# SME_tps63021.net
KiCad netlist of a schematic drawn in Altium Designer
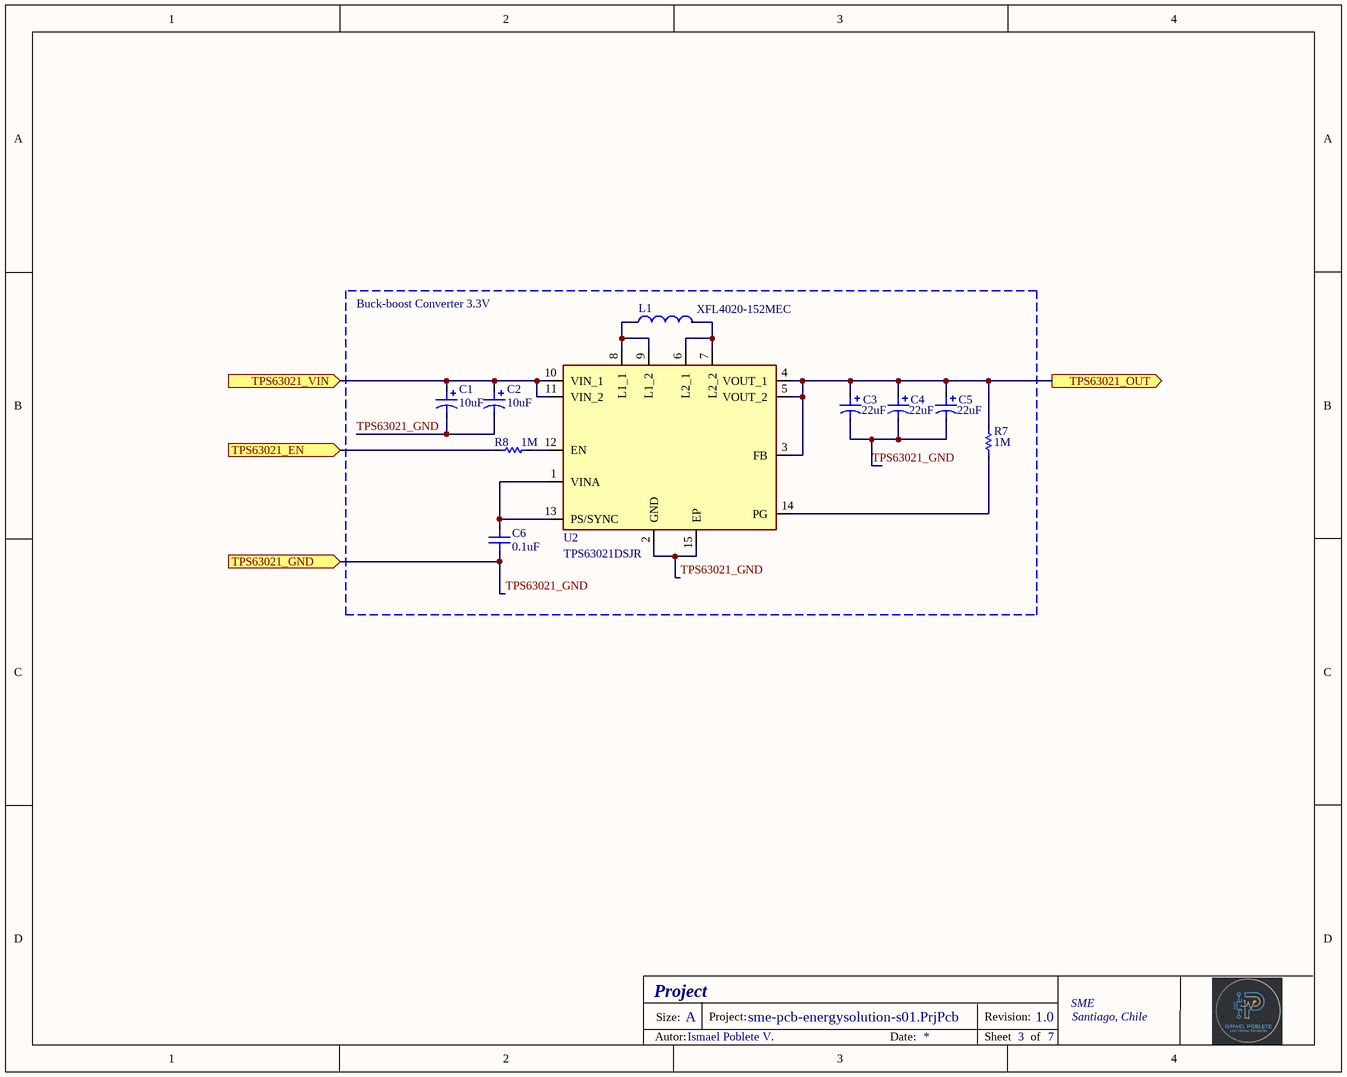
[diagram p0: SME_tps63021.SchDoc]

(export (version "E")
  (design (tool "Eeschema 10.0.6"))
  (components
    (comp (ref "C1")
      (value "T491A106M016AT")
      (footprint "CASE_A")
      (fields
        (field (name "MANUFACTURER") "Yageo Group")
        (field (name "TOLERANCE") "10%")
        (field (name "VOLTAGE") "16V")
        (field (name "CAPACITANCE") "10uF")
      )
      (libsource (lib "SME") (part "T491A106M016AT"))
    )
    (comp (ref "C2")
      (value "T491A106M016AT")
      (footprint "CASE_A")
      (fields
        (field (name "MANUFACTURER") "Yageo Group")
        (field (name "TOLERANCE") "10%")
        (field (name "VOLTAGE") "16V")
        (field (name "CAPACITANCE") "10uF")
      )
      (libsource (lib "SME") (part "T491A106M016AT"))
    )
    (comp (ref "C3")
      (value "T491B226K006AT")
      (footprint "T491B / CASE_B")
      (description "Tantalum Capacitors - Solid SMD 6.3V 22uF 1311 10% ESR=3.5ohms")
      (fields (field (name "CAPACITANCE") "22uF") (field (name "MANUFACTURER") "Yageo Group"))
      (libsource (lib "SME") (part "T491B226K006AT"))
    )
    (comp (ref "C4")
      (value "T491B226K006AT")
      (footprint "T491B / CASE_B")
      (description "Tantalum Capacitors - Solid SMD 6.3V 22uF 1311 10% ESR=3.5ohms")
      (fields (field (name "CAPACITANCE") "22uF") (field (name "MANUFACTURER") "Yageo Group"))
      (libsource (lib "SME") (part "T491B226K006AT"))
    )
    (comp (ref "C5")
      (value "T491B226K006AT")
      (footprint "T491B / CASE_B")
      (description "Tantalum Capacitors - Solid SMD 6.3V 22uF 1311 10% ESR=3.5ohms")
      (fields (field (name "CAPACITANCE") "22uF") (field (name "MANUFACTURER") "Yageo Group"))
      (libsource (lib "SME") (part "T491B226K006AT"))
    )
    (comp (ref "C6")
      (value "CC0603KRX7R9BB104")
      (footprint "C0603")
      (description "Multilayer Ceramic Capacitors MLCC - SMD/SMT 50 V 0.1uF X7R 0603 10%")
      (fields (field (name "CAPACITANCE") "0.1uF") (field (name "MANUFACTURER") "Yageo Group"))
      (libsource (lib "SME") (part "CC0603KRX7R9BB104"))
    )
    (comp (ref "L1")
      (value "XFL4020-152MEC")
      (footprint "XFL4020152MEC")
      (description "COILCRAFT - XFL4020-152MEC - Power Inductor (SMD), 1.5 H, 9.1 A, Shielded, 4.1 A, XFL4020")
      (fields
        (field (name "MOUSER PART NUMBER") "994-XFL4020-152MEC")
        (field (name "MANUFACTURER") "Coilcraft")
      )
      (libsource (lib "SME") (part "XFL4020-152MEC"))
    )
    (comp (ref "R7")
      (value "RT0603FRE071ML")
      (footprint "RES_0603")
      (description "Thin Film Resistors - SMD 1M OHM 1% 50PPM 1/10 W")
      (fields (field (name "RESISTANCE") "1M") (field (name "MANUFACTURER") "Yageo Group"))
      (libsource (lib "SME") (part "RT0603FRE071ML"))
    )
    (comp (ref "R8")
      (value "RT0603FRE071ML")
      (footprint "RES_0603")
      (description "Thin Film Resistors - SMD 1M OHM 1% 50PPM 1/10 W")
      (fields (field (name "RESISTANCE") "1M") (field (name "MANUFACTURER") "Yageo Group"))
      (libsource (lib "SME") (part "RT0603FRE071ML"))
    )
    (comp (ref "U2")
      (value "TPS63021DSJR")
      (footprint "VSON-14")
      (description "High Efficiency Single Inductor Buck-Boost Converter with 4A Switch")
      (fields
        (field (name "MOUSER PART NUMBER") "595-TPS63021DSJR")
        (field (name "MANUFACTURER") "Texas Instruments")
      )
      (libsource (lib "SME") (part "TPS63021DSJR"))
    )
  )
  (nets
    (net (code "1") (name "/TPS63021_EN") (class "Default")
      (node (ref "R8") (pin "1") (pinfunction "1_1") (pintype "passive"))
    )
    (net (code "2") (name "/TPS63021_GND") (class "Default")
      (node (ref "C1") (pin "2") (pinfunction "2_2") (pintype "passive"))
      (node (ref "C2") (pin "2") (pinfunction "2_2") (pintype "passive"))
      (node (ref "C3") (pin "2") (pinfunction "2_2") (pintype "passive"))
      (node (ref "C4") (pin "2") (pinfunction "2_2") (pintype "passive"))
      (node (ref "C5") (pin "2") (pinfunction "2_2") (pintype "passive"))
      (node (ref "C6") (pin "1") (pinfunction "1_1") (pintype "passive"))
      (node (ref "U2") (pin "15") (pinfunction "EP_15") (pintype "passive"))
      (node (ref "U2") (pin "2") (pinfunction "GND_2") (pintype "passive"))
    )
    (net (code "3") (name "/TPS63021_OUT") (class "Default")
      (node (ref "C3") (pin "1") (pinfunction "1_1") (pintype "passive"))
      (node (ref "C4") (pin "1") (pinfunction "1_1") (pintype "passive"))
      (node (ref "C5") (pin "1") (pinfunction "1_1") (pintype "passive"))
      (node (ref "R7") (pin "2") (pinfunction "2_2") (pintype "passive"))
      (node (ref "U2") (pin "3") (pinfunction "FB_3") (pintype "passive"))
      (node (ref "U2") (pin "4") (pinfunction "VOUT_1_4") (pintype "passive"))
      (node (ref "U2") (pin "5") (pinfunction "VOUT_2_5") (pintype "passive"))
    )
    (net (code "4") (name "/TPS63021_VIN") (class "Default")
      (node (ref "C1") (pin "1") (pinfunction "1_1") (pintype "passive"))
      (node (ref "C2") (pin "1") (pinfunction "1_1") (pintype "passive"))
      (node (ref "U2") (pin "10") (pinfunction "VIN_1_10") (pintype "passive"))
      (node (ref "U2") (pin "11") (pinfunction "VIN_2_11") (pintype "passive"))
    )
    (net (code "5") (name "Net-(U2-EN)") (class "Default")
      (node (ref "R8") (pin "2") (pinfunction "2_2") (pintype "passive"))
      (node (ref "U2") (pin "12") (pinfunction "EN_12") (pintype "passive"))
    )
    (net (code "6") (name "Net-(U2-L1_1)") (class "Default")
      (node (ref "L1") (pin "1") (pinfunction "1_1") (pintype "passive"))
      (node (ref "U2") (pin "8") (pinfunction "L1_1_8") (pintype "passive"))
      (node (ref "U2") (pin "9") (pinfunction "L1_2_9") (pintype "passive"))
    )
    (net (code "7") (name "Net-(U2-L2_1)") (class "Default")
      (node (ref "L1") (pin "2") (pinfunction "2_2") (pintype "passive"))
      (node (ref "U2") (pin "6") (pinfunction "L2_1_6") (pintype "passive"))
      (node (ref "U2") (pin "7") (pinfunction "L2_2_7") (pintype "passive"))
    )
    (net (code "8") (name "Net-(U2-PG)") (class "Default")
      (node (ref "R7") (pin "1") (pinfunction "1_1") (pintype "passive"))
      (node (ref "U2") (pin "14") (pinfunction "PG_14") (pintype "passive"))
    )
    (net (code "9") (name "Net-(U2-PS{slash}SYNC)") (class "Default")
      (node (ref "C6") (pin "2") (pinfunction "2_2") (pintype "passive"))
      (node (ref "U2") (pin "1") (pinfunction "VINA_1") (pintype "passive"))
      (node (ref "U2") (pin "13") (pinfunction "PS/SYNC_13") (pintype "passive"))
    )
  )
)
